# microcontroller.net
KiCad netlist of a schematic drawn in Altium Designer
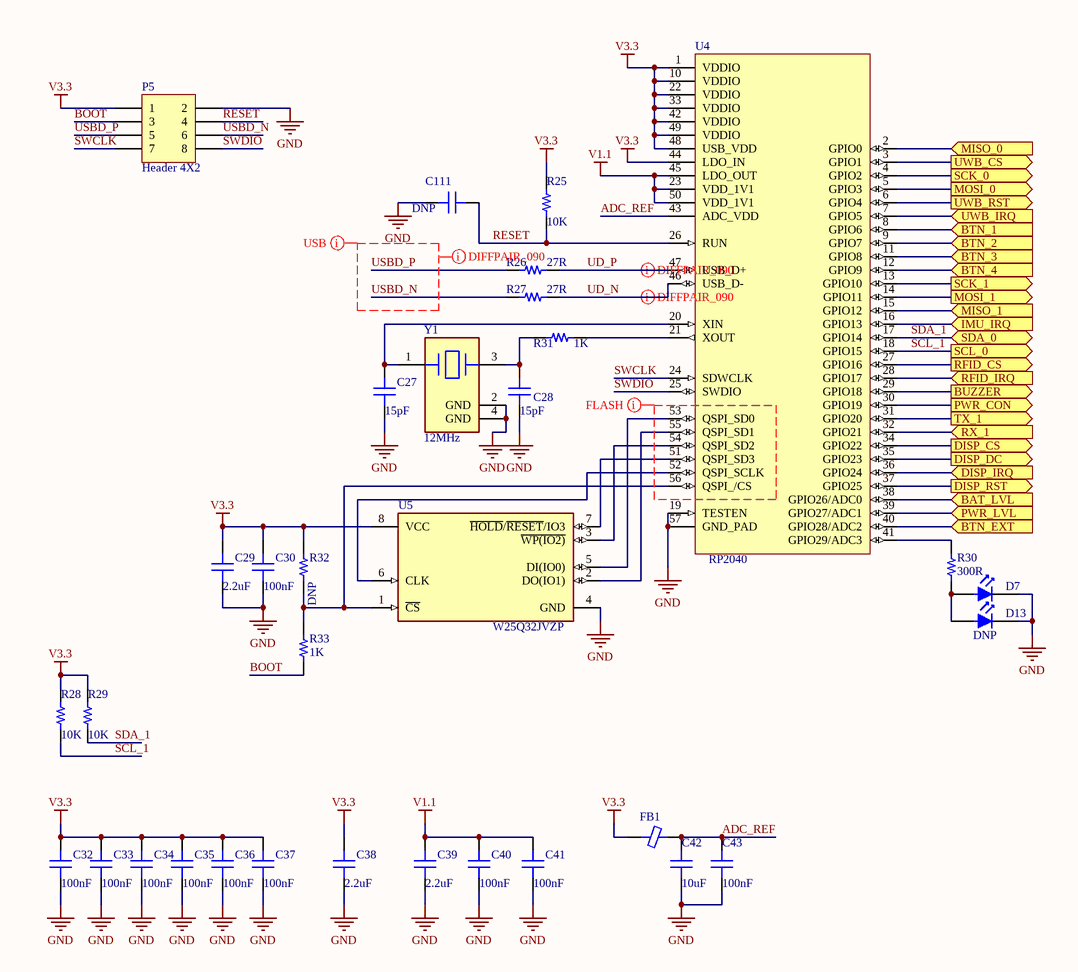
[diagram p0: microcontroller.SchDoc]

(export (version "E")
  (design (tool "Eeschema 10.0.6"))
  (components
    (comp (ref "C27")
      (value "15pF")
      (footprint "CAP 0603_1608")
      (description "SMT Capacitor")
      (fields (field (name "MF") "Murata") (field (name "MP") "GRM1885C1H150JA01J"))
      (libsource (lib "Capacitor") (part "Capacitor"))
    )
    (comp (ref "C28")
      (value "15pF")
      (footprint "CAP 0603_1608")
      (description "SMT Capacitor")
      (fields (field (name "MF") "Murata") (field (name "MP") "GRM1885C1H150JA01J"))
      (libsource (lib "Capacitor") (part "Capacitor"))
    )
    (comp (ref "C29")
      (value "2.2uF")
      (footprint "CAP 0603_1608")
      (description "SMT Capacitor")
      (fields (field (name "MF") "Samsung") (field (name "MP") "CL10A225KP8NNNC"))
      (libsource (lib "Capacitor") (part "Capacitor"))
    )
    (comp (ref "C30")
      (value "100nF")
      (footprint "CAP 0603_1608")
      (description "SMT Capacitor")
      (fields (field (name "MF") "TDK") (field (name "MP") "CGA3E2X7R1E104K080AA"))
      (libsource (lib "Capacitor") (part "Capacitor"))
    )
    (comp (ref "C32")
      (value "100nF")
      (footprint "CAP 0603_1608")
      (description "SMT Capacitor")
      (fields (field (name "MF") "TDK") (field (name "MP") "CGA3E2X7R1E104K080AA"))
      (libsource (lib "Capacitor") (part "Capacitor"))
    )
    (comp (ref "C33")
      (value "100nF")
      (footprint "CAP 0603_1608")
      (description "SMT Capacitor")
      (fields (field (name "MF") "TDK") (field (name "MP") "CGA3E2X7R1E104K080AA"))
      (libsource (lib "Capacitor") (part "Capacitor"))
    )
    (comp (ref "C34")
      (value "100nF")
      (footprint "CAP 0603_1608")
      (description "SMT Capacitor")
      (fields (field (name "MF") "TDK") (field (name "MP") "CGA3E2X7R1E104K080AA"))
      (libsource (lib "Capacitor") (part "Capacitor"))
    )
    (comp (ref "C35")
      (value "100nF")
      (footprint "CAP 0603_1608")
      (description "SMT Capacitor")
      (fields (field (name "MF") "TDK") (field (name "MP") "CGA3E2X7R1E104K080AA"))
      (libsource (lib "Capacitor") (part "Capacitor"))
    )
    (comp (ref "C36")
      (value "100nF")
      (footprint "CAP 0603_1608")
      (description "SMT Capacitor")
      (fields (field (name "MF") "TDK") (field (name "MP") "CGA3E2X7R1E104K080AA"))
      (libsource (lib "Capacitor") (part "Capacitor"))
    )
    (comp (ref "C37")
      (value "100nF")
      (footprint "CAP 0603_1608")
      (description "SMT Capacitor")
      (fields (field (name "MF") "TDK") (field (name "MP") "CGA3E2X7R1E104K080AA"))
      (libsource (lib "Capacitor") (part "Capacitor"))
    )
    (comp (ref "C38")
      (value "2.2uF")
      (footprint "CAP 0603_1608")
      (description "SMT Capacitor")
      (fields (field (name "MF") "Samsung") (field (name "MP") "CL10A225KP8NNNC"))
      (libsource (lib "Capacitor") (part "Capacitor"))
    )
    (comp (ref "C39")
      (value "2.2uF")
      (footprint "CAP 0603_1608")
      (description "SMT Capacitor")
      (fields (field (name "MF") "Samsung") (field (name "MP") "CL10A225KP8NNNC"))
      (libsource (lib "Capacitor") (part "Capacitor"))
    )
    (comp (ref "C40")
      (value "100nF")
      (footprint "CAP 0603_1608")
      (description "SMT Capacitor")
      (fields (field (name "MF") "TDK") (field (name "MP") "CGA3E2X7R1E104K080AA"))
      (libsource (lib "Capacitor") (part "Capacitor"))
    )
    (comp (ref "C41")
      (value "100nF")
      (footprint "CAP 0603_1608")
      (description "SMT Capacitor")
      (fields (field (name "MF") "TDK") (field (name "MP") "CGA3E2X7R1E104K080AA"))
      (libsource (lib "Capacitor") (part "Capacitor"))
    )
    (comp (ref "C42")
      (value "10uF")
      (footprint "CAP 0603_1608")
      (description "SMT Capacitor")
      (fields (field (name "MF") "Murata") (field (name "MP") "GRM188R61C106MAALD"))
      (libsource (lib "Capacitor") (part "Capacitor"))
    )
    (comp (ref "C43")
      (value "100nF")
      (footprint "CAP 0603_1608")
      (description "SMT Capacitor")
      (fields (field (name "MF") "TDK") (field (name "MP") "CGA3E2X7R1E104K080AA"))
      (libsource (lib "Capacitor") (part "Capacitor"))
    )
    (comp (ref "C111")
      (value "DNP")
      (footprint "CAP 0603_1608")
      (description "SMT Capacitor")
      (fields (field (name "MP") "C0603C104K4PACTU"))
      (libsource (lib "Capacitor") (part "Capacitor"))
    )
    (comp (ref "D7")
      (value "Green")
      (footprint "Würth_Elektronik_0_MFG")
      (description "Led Diffused SMD")
      (fields (field (name "MF") "LiteOn") (field (name "MP") "LTST-C190KGKT"))
      (libsource (lib "Diode") (part "LED SMD"))
    )
    (comp (ref "D13")
      (value "DNP")
      (footprint "Würth_Elektronik_0_MFG")
      (description "Led Diffused SMD")
      (fields (field (name "MF") "LiteOn") (field (name "MP") "LTST-C190KGKT"))
      (libsource (lib "Diode") (part "LED SMD"))
    )
    (comp (ref "FB1")
      (value "Ferrite Beads")
      (footprint "Murata_BLM18-0_15-t0_8_MFG")
      (description "SMT Ferrite Chip")
      (fields (field (name "MF") "Murata") (field (name "MP") "BLM18PG471SN1D"))
      (libsource (lib "Passive") (part "Ferrite Chip"))
    )
    (comp (ref "P5")
      (value "Header 4X2")
      (footprint "HDR2X4")
      (description "Header, 4-Pin, Dual row")
      (fields (field (name "PUBLISHER") "Altium Limited"))
      (libsource (lib "Connector") (part "Header 4X2"))
    )
    (comp (ref "R25")
      (value "10K")
      (footprint "RES 0603_1608")
      (description "SMT Resistor")
      (fields (field (name "MF") "YAGEO") (field (name "MP") "AC0603FR-0710KL"))
      (libsource (lib "Resistor") (part "Resistor"))
    )
    (comp (ref "R26")
      (value "27R")
      (footprint "RES 0603_1608")
      (description "SMT Resistor")
      (fields (field (name "MF") "YAGEO") (field (name "MP") "AC0603FR-0727RL"))
      (libsource (lib "Resistor") (part "Resistor"))
    )
    (comp (ref "R27")
      (value "27R")
      (footprint "RES 0603_1608")
      (description "SMT Resistor")
      (fields (field (name "MF") "YAGEO") (field (name "MP") "AC0603FR-0727RL"))
      (libsource (lib "Resistor") (part "Resistor"))
    )
    (comp (ref "R28")
      (value "10K")
      (footprint "RES 0603_1608")
      (description "SMT Resistor")
      (fields (field (name "MF") "YAGEO") (field (name "MP") "AC0603FR-0710KL"))
      (libsource (lib "Resistor") (part "Resistor"))
    )
    (comp (ref "R29")
      (value "10K")
      (footprint "RES 0603_1608")
      (description "SMT Resistor")
      (fields (field (name "MF") "YAGEO") (field (name "MP") "AC0603FR-0710KL"))
      (libsource (lib "Resistor") (part "Resistor"))
    )
    (comp (ref "R30")
      (value "300R")
      (footprint "RES 0603_1608")
      (description "SMT Resistor")
      (fields (field (name "MF") "YAGEO") (field (name "MP") "AC0603FR-07300RL"))
      (libsource (lib "Resistor") (part "Resistor"))
    )
    (comp (ref "R31")
      (value "1K")
      (footprint "RES 0603_1608")
      (description "SMT Resistor")
      (fields (field (name "MF") "YAGEO") (field (name "MP") "AC0603FR-071KL"))
      (libsource (lib "Resistor") (part "Resistor"))
    )
    (comp (ref "R32")
      (value "DNP")
      (footprint "RES 0603_1608")
      (description "SMT Resistor")
      (libsource (lib "Resistor") (part "Resistor"))
    )
    (comp (ref "R33")
      (value "1K")
      (footprint "RES 0603_1608")
      (description "SMT Resistor")
      (fields (field (name "MF") "YAGEO") (field (name "MP") "AC0603FR-071KL"))
      (libsource (lib "Resistor") (part "Resistor"))
    )
    (comp (ref "U4")
      (value "RP2040")
      (footprint "RP2040-Footprint-1")
      (fields (field (name "MF") "Raspberry Pi") (field (name "MP") "RP2040TR13"))
      (libsource (lib "RP2040") (part "RP2040"))
    )
    (comp (ref "U5")
      (value "W25Q32JVZP")
      (footprint "WINBOND WSON-8 6x5mm")
      (description "3V 32M-BIT SERIAL FLASH MEMORY WITH DUAL, QUAD SPI")
      (fields (field (name "MF") "Winbond") (field (name "MP") "W25Q32JVZPIQ"))
      (libsource (lib "Memory") (part "W25Q32JVZP"))
    )
    (comp (ref "Y1")
      (value "12MHz")
      (footprint "ABRACON ABM8G")
      (description "Crystals AEC-Q200 CRYSTAL 4pin SMD")
      (fields (field (name "MF") "ECS") (field (name "MP") "ECS-120-12-33-AGN-TR"))
      (libsource (lib "Crystal") (part "Crystal"))
    )
  )
  (nets
    (net (code "2") (name "/ADC_REF") (class "Default")
      (node (ref "C42") (pin "1") (pinfunction "1_1") (pintype "passive"))
      (node (ref "C43") (pin "1") (pinfunction "1_1") (pintype "passive"))
      (node (ref "FB1") (pin "2") (pinfunction "2_2") (pintype "passive"))
      (node (ref "U4") (pin "43") (pinfunction "ADC_VDD_43") (pintype "power_in"))
    )
    (net (code "3") (name "/BAT_LVL") (class "Default")
      (node (ref "U4") (pin "38") (pinfunction "GPIO26/ADC0_38") (pintype "bidirectional"))
    )
    (net (code "4") (name "/BOOT") (class "Default")
      (node (ref "P5") (pin "3") (pinfunction "3_3") (pintype "passive"))
      (node (ref "R33") (pin "1") (pinfunction "1_1") (pintype "passive"))
    )
    (net (code "5") (name "/BTN_1") (class "Default")
      (node (ref "U4") (pin "8") (pinfunction "GPIO6_8") (pintype "bidirectional"))
    )
    (net (code "6") (name "/BTN_2") (class "Default")
      (node (ref "U4") (pin "9") (pinfunction "GPIO7_9") (pintype "bidirectional"))
    )
    (net (code "7") (name "/BTN_3") (class "Default")
      (node (ref "U4") (pin "11") (pinfunction "GPIO8_11") (pintype "bidirectional"))
    )
    (net (code "8") (name "/BTN_4") (class "Default")
      (node (ref "U4") (pin "12") (pinfunction "GPIO9_12") (pintype "bidirectional"))
    )
    (net (code "9") (name "/BTN_EXT") (class "Default")
      (node (ref "U4") (pin "40") (pinfunction "GPIO28/ADC2_40") (pintype "bidirectional"))
    )
    (net (code "10") (name "/BUZZER") (class "Default")
      (node (ref "U4") (pin "29") (pinfunction "GPIO18_29") (pintype "bidirectional"))
    )
    (net (code "11") (name "/DISP_CS") (class "Default")
      (node (ref "U4") (pin "34") (pinfunction "GPIO22_34") (pintype "bidirectional"))
    )
    (net (code "12") (name "/DISP_DC") (class "Default")
      (node (ref "U4") (pin "35") (pinfunction "GPIO23_35") (pintype "bidirectional"))
    )
    (net (code "13") (name "/DISP_IRQ") (class "Default")
      (node (ref "U4") (pin "36") (pinfunction "GPIO24_36") (pintype "bidirectional"))
    )
    (net (code "14") (name "/DISP_RST") (class "Default")
      (node (ref "U4") (pin "37") (pinfunction "GPIO25_37") (pintype "bidirectional"))
    )
    (net (code "15") (name "/IMU_IRQ") (class "Default")
      (node (ref "U4") (pin "16") (pinfunction "GPIO13_16") (pintype "bidirectional"))
    )
    (net (code "16") (name "/MISO_0") (class "Default")
      (node (ref "U4") (pin "2") (pinfunction "GPIO0_2") (pintype "bidirectional"))
    )
    (net (code "17") (name "/MISO_1") (class "Default")
      (node (ref "U4") (pin "15") (pinfunction "GPIO12_15") (pintype "bidirectional"))
    )
    (net (code "18") (name "/MOSI_0") (class "Default")
      (node (ref "U4") (pin "5") (pinfunction "GPIO3_5") (pintype "bidirectional"))
    )
    (net (code "19") (name "/MOSI_1") (class "Default")
      (node (ref "U4") (pin "14") (pinfunction "GPIO11_14") (pintype "bidirectional"))
    )
    (net (code "20") (name "/PWR_CON") (class "Default")
      (node (ref "U4") (pin "30") (pinfunction "GPIO19_30") (pintype "bidirectional"))
    )
    (net (code "21") (name "/PWR_LVL") (class "Default")
      (node (ref "U4") (pin "39") (pinfunction "GPIO27/ADC1_39") (pintype "bidirectional"))
    )
    (net (code "22") (name "/RESET") (class "Default")
      (node (ref "C111") (pin "2") (pinfunction "2_2") (pintype "passive"))
      (node (ref "P5") (pin "4") (pinfunction "4_4") (pintype "passive"))
      (node (ref "R25") (pin "1") (pinfunction "1_1") (pintype "passive"))
      (node (ref "U4") (pin "26") (pinfunction "RUN_26") (pintype "input"))
    )
    (net (code "23") (name "/RFID_CS") (class "Default")
      (node (ref "U4") (pin "27") (pinfunction "GPIO16_27") (pintype "bidirectional"))
    )
    (net (code "24") (name "/RFID_IRQ") (class "Default")
      (node (ref "U4") (pin "28") (pinfunction "GPIO17_28") (pintype "bidirectional"))
    )
    (net (code "25") (name "/RX_1") (class "Default")
      (node (ref "U4") (pin "32") (pinfunction "GPIO21_32") (pintype "bidirectional"))
    )
    (net (code "26") (name "/SCK_0") (class "Default")
      (node (ref "U4") (pin "4") (pinfunction "GPIO2_4") (pintype "bidirectional"))
    )
    (net (code "27") (name "/SCK_1") (class "Default")
      (node (ref "U4") (pin "13") (pinfunction "GPIO10_13") (pintype "bidirectional"))
    )
    (net (code "28") (name "/SCL_1") (class "Default")
      (node (ref "R28") (pin "1") (pinfunction "1_1") (pintype "passive"))
      (node (ref "U4") (pin "18") (pinfunction "GPIO15_18") (pintype "bidirectional"))
    )
    (net (code "29") (name "/SDA_1") (class "Default")
      (node (ref "R29") (pin "1") (pinfunction "1_1") (pintype "passive"))
      (node (ref "U4") (pin "17") (pinfunction "GPIO14_17") (pintype "bidirectional"))
    )
    (net (code "30") (name "/SWCLK") (class "Default")
      (node (ref "P5") (pin "7") (pinfunction "7_7") (pintype "passive"))
      (node (ref "U4") (pin "24") (pinfunction "SDWCLK_24") (pintype "input"))
    )
    (net (code "31") (name "/SWDIO") (class "Default")
      (node (ref "P5") (pin "8") (pinfunction "8_8") (pintype "passive"))
      (node (ref "U4") (pin "25") (pinfunction "SWDIO_25") (pintype "bidirectional"))
    )
    (net (code "32") (name "/TX_1") (class "Default")
      (node (ref "U4") (pin "31") (pinfunction "GPIO20_31") (pintype "bidirectional"))
    )
    (net (code "33") (name "/UD_N") (class "Default")
      (node (ref "R27") (pin "2") (pinfunction "2_2") (pintype "passive"))
      (node (ref "U4") (pin "46") (pinfunction "USB_D-_46") (pintype "bidirectional"))
    )
    (net (code "34") (name "/UD_P") (class "Default")
      (node (ref "R26") (pin "2") (pinfunction "2_2") (pintype "passive"))
      (node (ref "U4") (pin "47") (pinfunction "USB_D+_47") (pintype "bidirectional"))
    )
    (net (code "35") (name "/USBD_N") (class "Default")
      (node (ref "P5") (pin "6") (pinfunction "6_6") (pintype "passive"))
      (node (ref "R27") (pin "1") (pinfunction "1_1") (pintype "passive"))
    )
    (net (code "36") (name "/USBD_P") (class "Default")
      (node (ref "P5") (pin "5") (pinfunction "5_5") (pintype "passive"))
      (node (ref "R26") (pin "1") (pinfunction "1_1") (pintype "passive"))
    )
    (net (code "37") (name "/UWB_CS") (class "Default")
      (node (ref "U4") (pin "3") (pinfunction "GPIO1_3") (pintype "bidirectional"))
    )
    (net (code "38") (name "/UWB_IRQ") (class "Default")
      (node (ref "U4") (pin "7") (pinfunction "GPIO5_7") (pintype "bidirectional"))
    )
    (net (code "39") (name "/UWB_RST") (class "Default")
      (node (ref "U4") (pin "6") (pinfunction "GPIO4_6") (pintype "bidirectional"))
    )
    (net (code "40") (name "GND") (class "Default")
      (node (ref "C111") (pin "1") (pinfunction "1_1") (pintype "passive"))
      (node (ref "C27") (pin "1") (pinfunction "1_1") (pintype "passive"))
      (node (ref "C28") (pin "1") (pinfunction "1_1") (pintype "passive"))
      (node (ref "C29") (pin "2") (pinfunction "2_2") (pintype "passive"))
      (node (ref "C30") (pin "2") (pinfunction "2_2") (pintype "passive"))
      (node (ref "C32") (pin "2") (pinfunction "2_2") (pintype "passive"))
      (node (ref "C33") (pin "2") (pinfunction "2_2") (pintype "passive"))
      (node (ref "C34") (pin "2") (pinfunction "2_2") (pintype "passive"))
      (node (ref "C35") (pin "2") (pinfunction "2_2") (pintype "passive"))
      (node (ref "C36") (pin "2") (pinfunction "2_2") (pintype "passive"))
      (node (ref "C37") (pin "2") (pinfunction "2_2") (pintype "passive"))
      (node (ref "C38") (pin "2") (pinfunction "2_2") (pintype "passive"))
      (node (ref "C39") (pin "2") (pinfunction "2_2") (pintype "passive"))
      (node (ref "C40") (pin "2") (pinfunction "2_2") (pintype "passive"))
      (node (ref "C41") (pin "2") (pinfunction "2_2") (pintype "passive"))
      (node (ref "C42") (pin "2") (pinfunction "2_2") (pintype "passive"))
      (node (ref "C43") (pin "2") (pinfunction "2_2") (pintype "passive"))
      (node (ref "D13") (pin "1") (pinfunction "C_1") (pintype "passive"))
      (node (ref "D7") (pin "1") (pinfunction "C_1") (pintype "passive"))
      (node (ref "P5") (pin "2") (pinfunction "2_2") (pintype "passive"))
      (node (ref "U4") (pin "19") (pinfunction "TESTEN_19") (pintype "input"))
      (node (ref "U4") (pin "57") (pinfunction "GND_PAD_57") (pintype "power_in"))
      (node (ref "U5") (pin "4") (pinfunction "GND_4") (pintype "power_in"))
      (node (ref "Y1") (pin "2") (pinfunction "GND_2") (pintype "power_in"))
      (node (ref "Y1") (pin "4") (pinfunction "GND_4") (pintype "power_in"))
    )
    (net (code "41") (name "Net-(C28-Pad2)") (class "Default")
      (node (ref "C28") (pin "2") (pinfunction "2_2") (pintype "passive"))
      (node (ref "R31") (pin "1") (pinfunction "1_1") (pintype "passive"))
      (node (ref "Y1") (pin "3") (pinfunction "3_3") (pintype "passive"))
    )
    (net (code "42") (name "Net-(D13-A)") (class "Default")
      (node (ref "D13") (pin "2") (pinfunction "A_2") (pintype "passive"))
      (node (ref "D7") (pin "2") (pinfunction "A_2") (pintype "passive"))
      (node (ref "R30") (pin "2") (pinfunction "2_2") (pintype "passive"))
    )
    (net (code "43") (name "Net-(U4-GPIO29{slash}ADC3)") (class "Default")
      (node (ref "R30") (pin "1") (pinfunction "1_1") (pintype "passive"))
      (node (ref "U4") (pin "41") (pinfunction "GPIO29/ADC3_41") (pintype "bidirectional"))
    )
    (net (code "44") (name "Net-(U4-QSPI_SCLK)") (class "Default")
      (node (ref "U4") (pin "52") (pinfunction "QSPI_SCLK_52") (pintype "bidirectional"))
      (node (ref "U5") (pin "6") (pinfunction "CLK_6") (pintype "input"))
    )
    (net (code "45") (name "Net-(U4-QSPI_SD0)") (class "Default")
      (node (ref "U4") (pin "53") (pinfunction "QSPI_SD0_53") (pintype "bidirectional"))
      (node (ref "U5") (pin "5") (pinfunction "DI(IO0)_5") (pintype "bidirectional"))
    )
    (net (code "46") (name "Net-(U4-QSPI_SD1)") (class "Default")
      (node (ref "U4") (pin "55") (pinfunction "QSPI_SD1_55") (pintype "bidirectional"))
      (node (ref "U5") (pin "2") (pinfunction "DO(IO1)_2") (pintype "bidirectional"))
    )
    (net (code "47") (name "Net-(U4-QSPI_SD2)") (class "Default")
      (node (ref "U4") (pin "54") (pinfunction "QSPI_SD2_54") (pintype "bidirectional"))
      (node (ref "U5") (pin "3") (pinfunction "~{WP(IO2)}_3") (pintype "bidirectional"))
    )
    (net (code "48") (name "Net-(U4-QSPI_SD3)") (class "Default")
      (node (ref "U4") (pin "51") (pinfunction "QSPI_SD3_51") (pintype "bidirectional"))
      (node (ref "U5") (pin "7") (pinfunction "~{HOLD}/~{RESET}/IO3_7") (pintype "bidirectional"))
    )
    (net (code "49") (name "Net-(U4-QSPI_{slash}CS)") (class "Default")
      (node (ref "R32") (pin "2") (pinfunction "2_2") (pintype "passive"))
      (node (ref "R33") (pin "2") (pinfunction "2_2") (pintype "passive"))
      (node (ref "U4") (pin "56") (pinfunction "QSPI_/CS_56") (pintype "bidirectional"))
      (node (ref "U5") (pin "1") (pinfunction "~{CS}_1") (pintype "input"))
    )
    (net (code "50") (name "Net-(U4-XIN)") (class "Default")
      (node (ref "C27") (pin "2") (pinfunction "2_2") (pintype "passive"))
      (node (ref "U4") (pin "20") (pinfunction "XIN_20") (pintype "input"))
      (node (ref "Y1") (pin "1") (pinfunction "1_1") (pintype "passive"))
    )
    (net (code "51") (name "Net-(U4-XOUT)") (class "Default")
      (node (ref "R31") (pin "2") (pinfunction "2_2") (pintype "passive"))
      (node (ref "U4") (pin "21") (pinfunction "XOUT_21") (pintype "output"))
    )
    (net (code "52") (name "V1.1") (class "Default")
      (node (ref "C39") (pin "1") (pinfunction "1_1") (pintype "passive"))
      (node (ref "C40") (pin "1") (pinfunction "1_1") (pintype "passive"))
      (node (ref "C41") (pin "1") (pinfunction "1_1") (pintype "passive"))
      (node (ref "U4") (pin "23") (pinfunction "VDD_1V1_23") (pintype "power_in"))
      (node (ref "U4") (pin "45") (pinfunction "LDO_OUT_45") (pintype "power_in"))
      (node (ref "U4") (pin "50") (pinfunction "VDD_1V1_50") (pintype "power_in"))
    )
    (net (code "53") (name "V3.3") (class "Default")
      (node (ref "C29") (pin "1") (pinfunction "1_1") (pintype "passive"))
      (node (ref "C30") (pin "1") (pinfunction "1_1") (pintype "passive"))
      (node (ref "C32") (pin "1") (pinfunction "1_1") (pintype "passive"))
      (node (ref "C33") (pin "1") (pinfunction "1_1") (pintype "passive"))
      (node (ref "C34") (pin "1") (pinfunction "1_1") (pintype "passive"))
      (node (ref "C35") (pin "1") (pinfunction "1_1") (pintype "passive"))
      (node (ref "C36") (pin "1") (pinfunction "1_1") (pintype "passive"))
      (node (ref "C37") (pin "1") (pinfunction "1_1") (pintype "passive"))
      (node (ref "C38") (pin "1") (pinfunction "1_1") (pintype "passive"))
      (node (ref "FB1") (pin "1") (pinfunction "1_1") (pintype "passive"))
      (node (ref "P5") (pin "1") (pinfunction "1_1") (pintype "passive"))
      (node (ref "R25") (pin "2") (pinfunction "2_2") (pintype "passive"))
      (node (ref "R28") (pin "2") (pinfunction "2_2") (pintype "passive"))
      (node (ref "R29") (pin "2") (pinfunction "2_2") (pintype "passive"))
      (node (ref "R32") (pin "1") (pinfunction "1_1") (pintype "passive"))
      (node (ref "U4") (pin "1") (pinfunction "VDDIO_1") (pintype "power_in"))
      (node (ref "U4") (pin "10") (pinfunction "VDDIO_10") (pintype "power_in"))
      (node (ref "U4") (pin "22") (pinfunction "VDDIO_22") (pintype "power_in"))
      (node (ref "U4") (pin "33") (pinfunction "VDDIO_33") (pintype "power_in"))
      (node (ref "U4") (pin "42") (pinfunction "VDDIO_42") (pintype "power_in"))
      (node (ref "U4") (pin "44") (pinfunction "LDO_IN_44") (pintype "power_in"))
      (node (ref "U4") (pin "48") (pinfunction "USB_VDD_48") (pintype "power_in"))
      (node (ref "U4") (pin "49") (pinfunction "VDDIO_49") (pintype "power_in"))
      (node (ref "U5") (pin "8") (pinfunction "VCC_8") (pintype "power_in"))
    )
  )
)
